# Gamma-BOTTOM-Version2.net
KiCad netlist of a schematic drawn in EAGLE
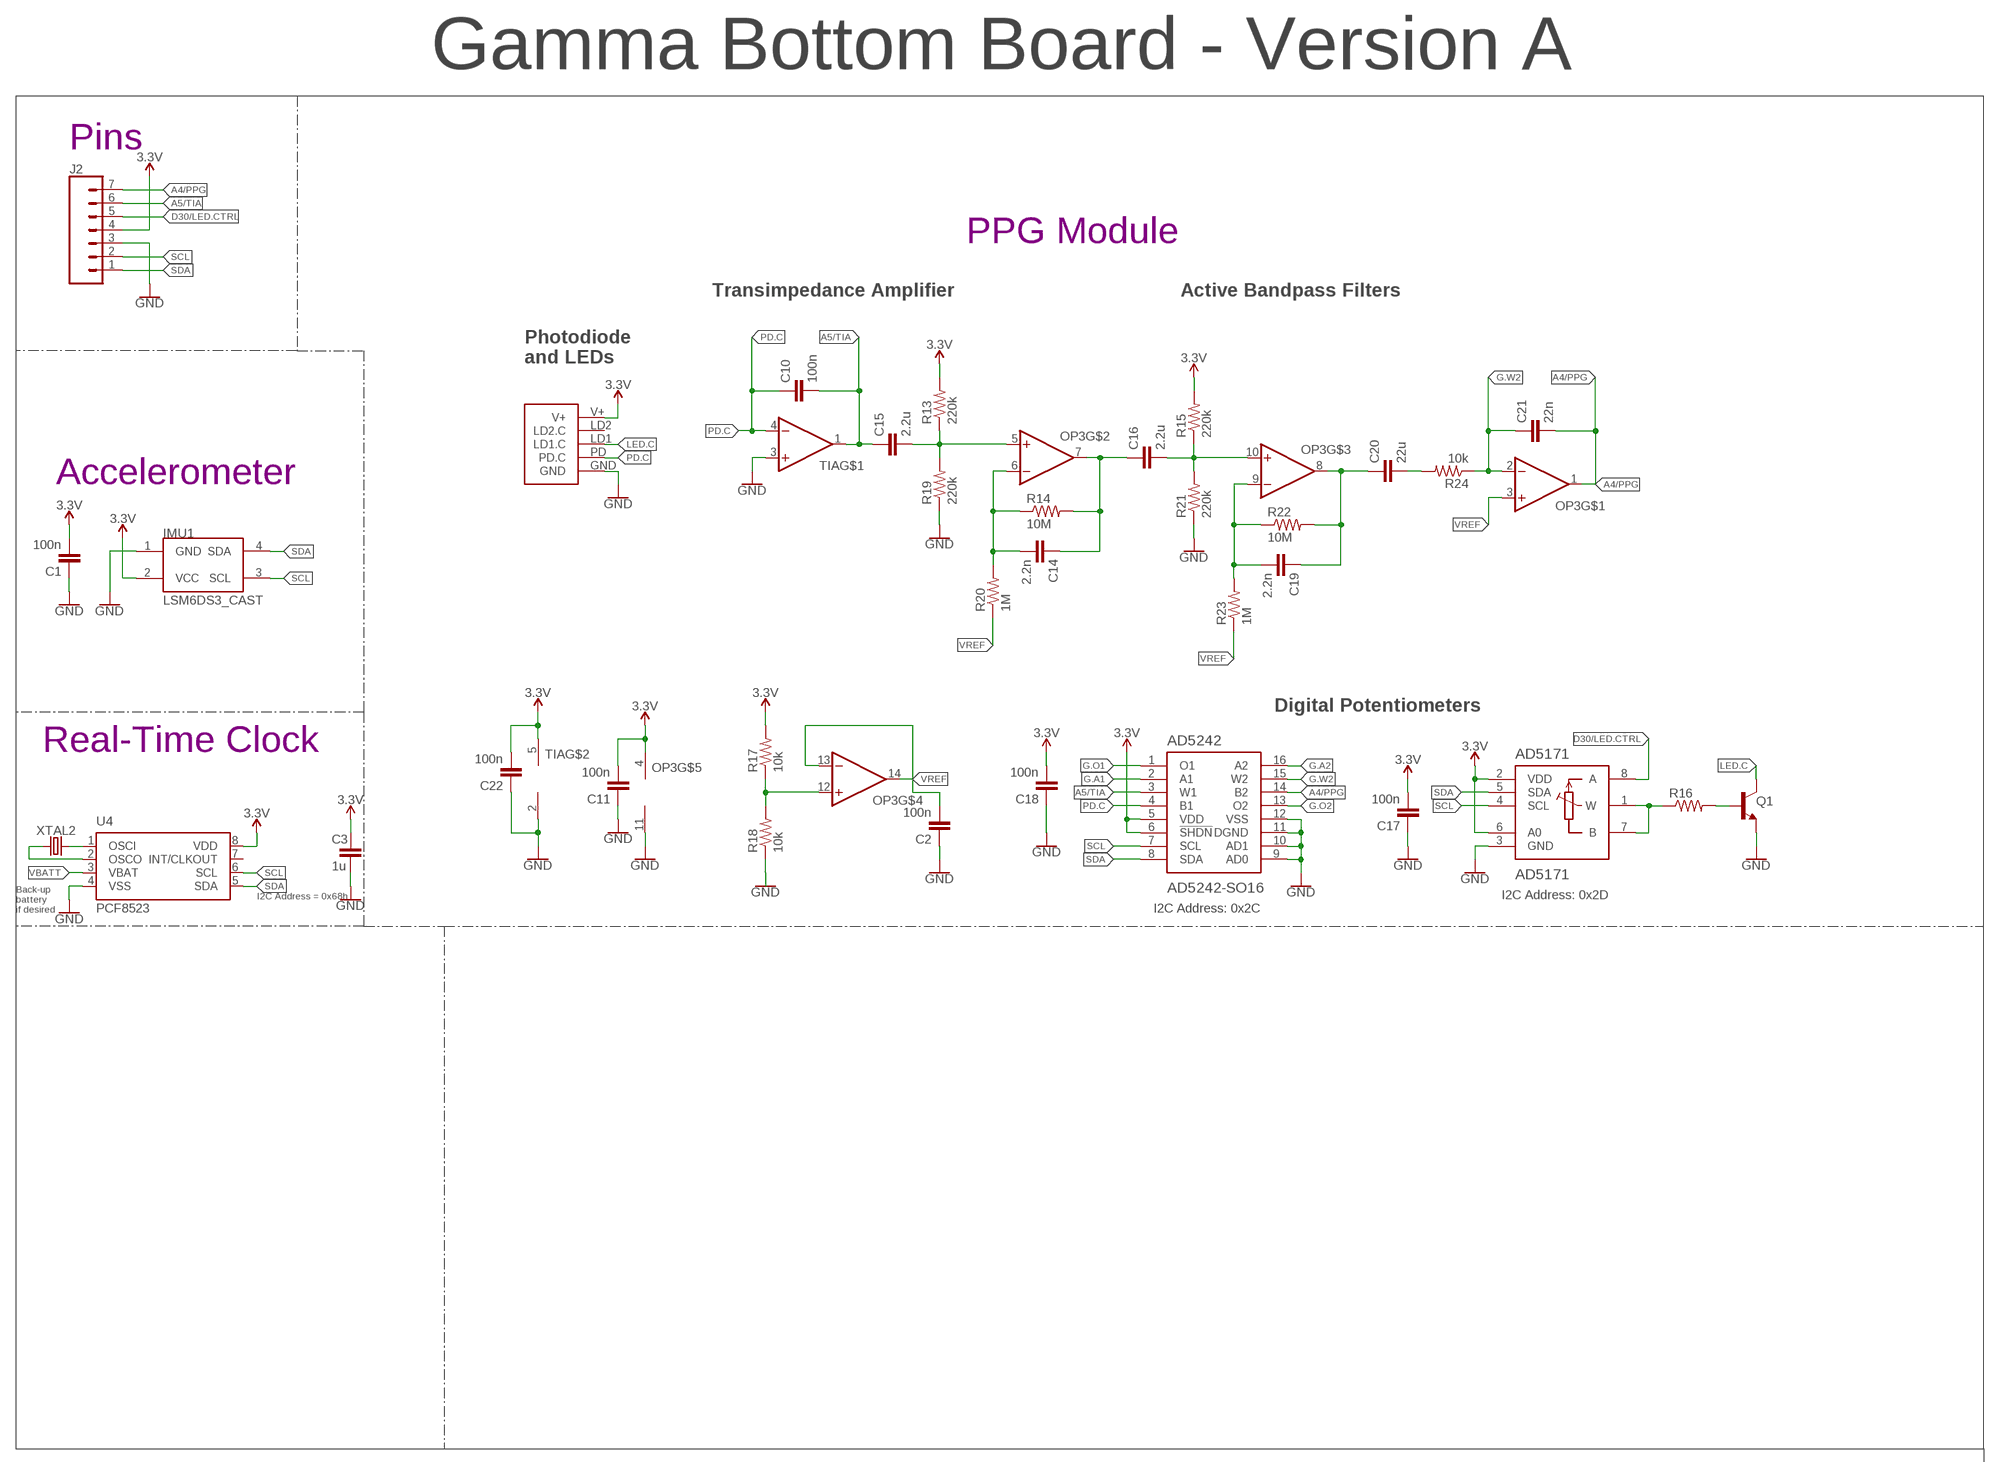
[diagram p0: schematic, sheet 1]

(export (version "E")
  (design (tool "Eeschema 10.0.6"))
  (components
    (comp (ref "AD5171")
      (value "AD5171")
      (footprint "eagle-import:SOT-23-8")
      (libsource (lib "eagle-import") (part "AD5171"))
    )
    (comp (ref "AD5242")
      (value "AD5242-SO16")
      (footprint "eagle-import:SO16")
      (libsource (lib "eagle-import") (part "AD5242-SO16"))
    )
    (comp (ref "C1")
      (value "100n")
      (footprint "eagle-import:C0603")
      (libsource (lib "eagle-import") (part "CAPACITOR0603"))
    )
    (comp (ref "C2")
      (value "100n")
      (footprint "eagle-import:C0603")
      (libsource (lib "eagle-import") (part "CAPACITOR0603"))
    )
    (comp (ref "C3")
      (value "1u")
      (footprint "eagle-import:C0603")
      (libsource (lib "eagle-import") (part "CAPACITOR0603"))
    )
    (comp (ref "C10")
      (value "100n")
      (footprint "eagle-import:C0603")
      (libsource (lib "eagle-import") (part "CAPACITOR0603"))
    )
    (comp (ref "C11")
      (value "100n")
      (footprint "eagle-import:C0603")
      (libsource (lib "eagle-import") (part "CAPACITOR0603"))
    )
    (comp (ref "C14")
      (value "2.2n")
      (footprint "eagle-import:C0603")
      (libsource (lib "eagle-import") (part "CAPACITOR0603"))
    )
    (comp (ref "C15")
      (value "2.2u")
      (footprint "eagle-import:C0603")
      (libsource (lib "eagle-import") (part "CAPACITOR0603"))
    )
    (comp (ref "C16")
      (value "2.2u")
      (footprint "eagle-import:C0603")
      (libsource (lib "eagle-import") (part "CAPACITOR0603"))
    )
    (comp (ref "C17")
      (value "100n")
      (footprint "eagle-import:C0603")
      (libsource (lib "eagle-import") (part "CAPACITOR0603"))
    )
    (comp (ref "C18")
      (value "100n")
      (footprint "eagle-import:C0603")
      (libsource (lib "eagle-import") (part "CAPACITOR0603"))
    )
    (comp (ref "C19")
      (value "2.2n")
      (footprint "eagle-import:C0603")
      (libsource (lib "eagle-import") (part "CAPACITOR0603"))
    )
    (comp (ref "C20")
      (value "22u")
      (footprint "eagle-import:C0603")
      (libsource (lib "eagle-import") (part "CAPACITOR0603"))
    )
    (comp (ref "C21")
      (value "22n")
      (footprint "eagle-import:C0603")
      (libsource (lib "eagle-import") (part "CAPACITOR0603"))
    )
    (comp (ref "C22")
      (value "100n")
      (footprint "eagle-import:C0603")
      (libsource (lib "eagle-import") (part "CAPACITOR0603"))
    )
    (comp (ref "IMU1")
      (value "LSM6DS3_CAST")
      (footprint "eagle-import:LSM6DS3_CAST")
      (libsource (lib "eagle-import") (part "LSM6DS3_CAST"))
    )
    (comp (ref "J2")
      (value "CONN_07-1.27MM")
      (footprint "eagle-import:1X07_1.27MM")
      (libsource (lib "eagle-import") (part "CONN_07-1.27MM"))
    )
    (comp (ref "OP3")
      (value "OP-QUAD-SO14")
      (footprint "eagle-import:SO14")
      (libsource (lib "eagle-import") (part "OP-QUAD-SO14"))
    )
    (comp (ref "Q1")
      (value "NPN-GENERIC")
      (footprint "eagle-import:SOT23-3")
      (libsource (lib "eagle-import") (part "NPN-GENERIC"))
    )
    (comp (ref "R13")
      (value "220k")
      (footprint "eagle-import:R0603")
      (libsource (lib "eagle-import") (part "RESISTOR0603"))
    )
    (comp (ref "R14")
      (value "10M")
      (footprint "eagle-import:R0603")
      (libsource (lib "eagle-import") (part "RESISTOR0603"))
    )
    (comp (ref "R15")
      (value "220k")
      (footprint "eagle-import:R0603")
      (libsource (lib "eagle-import") (part "RESISTOR0603"))
    )
    (comp (ref "R16")
      (value "RESISTOR0603")
      (footprint "eagle-import:R0603")
      (libsource (lib "eagle-import") (part "RESISTOR0603"))
    )
    (comp (ref "R17")
      (value "10k")
      (footprint "eagle-import:R0402")
      (libsource (lib "eagle-import") (part "RESISTOR0402"))
    )
    (comp (ref "R18")
      (value "10k")
      (footprint "eagle-import:R0402")
      (libsource (lib "eagle-import") (part "RESISTOR0402"))
    )
    (comp (ref "R19")
      (value "220k")
      (footprint "eagle-import:R0603")
      (libsource (lib "eagle-import") (part "RESISTOR0603"))
    )
    (comp (ref "R20")
      (value "1M")
      (footprint "eagle-import:R0603")
      (libsource (lib "eagle-import") (part "RESISTOR0603"))
    )
    (comp (ref "R21")
      (value "220k")
      (footprint "eagle-import:R0603")
      (libsource (lib "eagle-import") (part "RESISTOR0603"))
    )
    (comp (ref "R22")
      (value "10M")
      (footprint "eagle-import:R0603")
      (libsource (lib "eagle-import") (part "RESISTOR0603"))
    )
    (comp (ref "R23")
      (value "1M")
      (footprint "eagle-import:R0603")
      (libsource (lib "eagle-import") (part "RESISTOR0603"))
    )
    (comp (ref "R24")
      (value "10k")
      (footprint "eagle-import:R0603")
      (libsource (lib "eagle-import") (part "RESISTOR0603"))
    )
    (comp (ref "TIA")
      (value "OP-SINGLEOT")
      (footprint "eagle-import:SOT23-5")
      (libsource (lib "eagle-import") (part "OP-SINGLEOT"))
    )
    (comp (ref "U$3")
      (value "PPG.MODULE.2")
      (footprint "eagle-import:PPG.MODULE.2")
      (libsource (lib "eagle-import") (part "PPG.MODULE.2"))
    )
    (comp (ref "U4")
      (value "PCF8523")
      (footprint "eagle-import:SO8")
      (libsource (lib "eagle-import") (part "PCF8523"))
    )
    (comp (ref "XTAL2")
      (value "32.7680kHz")
      (footprint "eagle-import:2-SMD.NOLEAD.2.0MMTO1.2MM")
      (fields (field (name "FREQ") "32.7680KHZ"))
      (libsource (lib "eagle-import") (part "CRYSTALECS-.327-12.5-12-C-TR"))
    )
  )
  (nets
    (net (code "1") (name "3.3V") (class "Default")
      (node (ref "AD5171") (pin "2") (pinfunction "VDD_2") (pintype "bidirectional"))
      (node (ref "AD5171") (pin "6") (pinfunction "A0_6") (pintype "bidirectional"))
      (node (ref "AD5242") (pin "5") (pinfunction "VDD_5") (pintype "bidirectional"))
      (node (ref "AD5242") (pin "6") (pinfunction "~{SHDN}_6") (pintype "bidirectional"))
      (node (ref "C1") (pin "2") (pinfunction "2_2") (pintype "passive"))
      (node (ref "C11") (pin "2") (pinfunction "2_2") (pintype "passive"))
      (node (ref "C17") (pin "2") (pinfunction "2_2") (pintype "passive"))
      (node (ref "C18") (pin "2") (pinfunction "2_2") (pintype "passive"))
      (node (ref "C22") (pin "2") (pinfunction "2_2") (pintype "passive"))
      (node (ref "C3") (pin "1") (pinfunction "1_1") (pintype "passive"))
      (node (ref "IMU1") (pin "2") (pinfunction "VCC_2") (pintype "bidirectional"))
      (node (ref "J2") (pin "4") (pinfunction "4_4") (pintype "passive"))
      (node (ref "OP3") (pin "4") (pinfunction "V+_4") (pintype "power_in"))
      (node (ref "R13") (pin "2") (pinfunction "2_2") (pintype "passive"))
      (node (ref "R15") (pin "2") (pinfunction "2_2") (pintype "passive"))
      (node (ref "R17") (pin "2") (pinfunction "2_2") (pintype "passive"))
      (node (ref "TIA") (pin "5") (pinfunction "V+_5") (pintype "power_in"))
      (node (ref "U$3") (pin "V+") (pinfunction "V+_V+") (pintype "bidirectional"))
      (node (ref "U4") (pin "8") (pinfunction "VDD_8") (pintype "power_in"))
    )
    (net (code "2") (name "A4{slash}PPG") (class "Default")
      (node (ref "AD5242") (pin "14") (pinfunction "B2_14") (pintype "bidirectional"))
      (node (ref "C21") (pin "2") (pinfunction "2_2") (pintype "passive"))
      (node (ref "J2") (pin "7") (pinfunction "7_7") (pintype "passive"))
      (node (ref "OP3") (pin "1") (pinfunction "OUT_1") (pintype "output"))
    )
    (net (code "3") (name "A5{slash}TIA") (class "Default")
      (node (ref "AD5242") (pin "3") (pinfunction "W1_3") (pintype "bidirectional"))
      (node (ref "C10") (pin "2") (pinfunction "2_2") (pintype "passive"))
      (node (ref "C15") (pin "1") (pinfunction "1_1") (pintype "passive"))
      (node (ref "J2") (pin "6") (pinfunction "6_6") (pintype "passive"))
      (node (ref "TIA") (pin "1") (pinfunction "OUT_1") (pintype "output"))
    )
    (net (code "4") (name "D30{slash}LED.CTRL") (class "Default")
      (node (ref "AD5171") (pin "8") (pinfunction "A_8") (pintype "bidirectional"))
      (node (ref "J2") (pin "5") (pinfunction "5_5") (pintype "passive"))
    )
    (net (code "5") (name "G.A1") (class "Default")
      (node (ref "AD5242") (pin "2") (pinfunction "A1_2") (pintype "bidirectional"))
    )
    (net (code "6") (name "G.A2") (class "Default")
      (node (ref "AD5242") (pin "16") (pinfunction "A2_16") (pintype "bidirectional"))
    )
    (net (code "7") (name "G.O1") (class "Default")
      (node (ref "AD5242") (pin "1") (pinfunction "O1_1") (pintype "bidirectional"))
    )
    (net (code "8") (name "G.O2") (class "Default")
      (node (ref "AD5242") (pin "13") (pinfunction "O2_13") (pintype "bidirectional"))
    )
    (net (code "9") (name "G.W2") (class "Default")
      (node (ref "AD5242") (pin "15") (pinfunction "W2_15") (pintype "bidirectional"))
      (node (ref "C21") (pin "1") (pinfunction "1_1") (pintype "passive"))
      (node (ref "OP3") (pin "2") (pinfunction "-IN_2") (pintype "input"))
      (node (ref "R24") (pin "1") (pinfunction "1_1") (pintype "passive"))
    )
    (net (code "10") (name "GND") (class "Default")
      (node (ref "AD5171") (pin "3") (pinfunction "GND_3") (pintype "bidirectional"))
      (node (ref "AD5242") (pin "10") (pinfunction "AD1_10") (pintype "bidirectional"))
      (node (ref "AD5242") (pin "11") (pinfunction "DGND_11") (pintype "bidirectional"))
      (node (ref "AD5242") (pin "12") (pinfunction "VSS_12") (pintype "bidirectional"))
      (node (ref "AD5242") (pin "9") (pinfunction "AD0_9") (pintype "bidirectional"))
      (node (ref "C1") (pin "1") (pinfunction "1_1") (pintype "passive"))
      (node (ref "C11") (pin "1") (pinfunction "1_1") (pintype "passive"))
      (node (ref "C17") (pin "1") (pinfunction "1_1") (pintype "passive"))
      (node (ref "C18") (pin "1") (pinfunction "1_1") (pintype "passive"))
      (node (ref "C2") (pin "1") (pinfunction "1_1") (pintype "passive"))
      (node (ref "C22") (pin "1") (pinfunction "1_1") (pintype "passive"))
      (node (ref "C3") (pin "2") (pinfunction "2_2") (pintype "passive"))
      (node (ref "IMU1") (pin "1") (pinfunction "GND_1") (pintype "bidirectional"))
      (node (ref "J2") (pin "3") (pinfunction "3_3") (pintype "passive"))
      (node (ref "OP3") (pin "11") (pinfunction "V-_11") (pintype "power_in"))
      (node (ref "Q1") (pin "2") (pinfunction "E_2") (pintype "passive"))
      (node (ref "R18") (pin "1") (pinfunction "1_1") (pintype "passive"))
      (node (ref "R19") (pin "1") (pinfunction "1_1") (pintype "passive"))
      (node (ref "R21") (pin "1") (pinfunction "1_1") (pintype "passive"))
      (node (ref "TIA") (pin "2") (pinfunction "V-_2") (pintype "power_in"))
      (node (ref "TIA") (pin "3") (pinfunction "+IN_3") (pintype "input"))
      (node (ref "U$3") (pin "GND") (pinfunction "GND_GND") (pintype "bidirectional"))
      (node (ref "U4") (pin "4") (pinfunction "VSS_4") (pintype "power_in"))
    )
    (net (code "11") (name "LED.C") (class "Default")
      (node (ref "Q1") (pin "3") (pinfunction "C_3") (pintype "passive"))
      (node (ref "U$3") (pin "LD1") (pinfunction "LD1.C_LD1") (pintype "bidirectional"))
    )
    (net (code "12") (name "Net-(AD5171-B)") (class "Default")
      (node (ref "AD5171") (pin "1") (pinfunction "W_1") (pintype "bidirectional"))
      (node (ref "AD5171") (pin "7") (pinfunction "B_7") (pintype "bidirectional"))
      (node (ref "R16") (pin "1") (pinfunction "1_1") (pintype "passive"))
    )
    (net (code "13") (name "Net-(C20-Pad2)") (class "Default")
      (node (ref "C20") (pin "2") (pinfunction "2_2") (pintype "passive"))
      (node (ref "R24") (pin "2") (pinfunction "2_2") (pintype "passive"))
    )
    (net (code "14") (name "Net-(OP3B-+IN)") (class "Default")
      (node (ref "C15") (pin "2") (pinfunction "2_2") (pintype "passive"))
      (node (ref "OP3") (pin "5") (pinfunction "+IN_5") (pintype "input"))
      (node (ref "R13") (pin "1") (pinfunction "1_1") (pintype "passive"))
      (node (ref "R19") (pin "2") (pinfunction "2_2") (pintype "passive"))
    )
    (net (code "15") (name "Net-(OP3B--IN)") (class "Default")
      (node (ref "C14") (pin "2") (pinfunction "2_2") (pintype "passive"))
      (node (ref "OP3") (pin "6") (pinfunction "-IN_6") (pintype "input"))
      (node (ref "R14") (pin "1") (pinfunction "1_1") (pintype "passive"))
      (node (ref "R20") (pin "2") (pinfunction "2_2") (pintype "passive"))
    )
    (net (code "16") (name "Net-(OP3B-OUT)") (class "Default")
      (node (ref "C14") (pin "1") (pinfunction "1_1") (pintype "passive"))
      (node (ref "C16") (pin "1") (pinfunction "1_1") (pintype "passive"))
      (node (ref "OP3") (pin "7") (pinfunction "OUT_7") (pintype "output"))
      (node (ref "R14") (pin "2") (pinfunction "2_2") (pintype "passive"))
    )
    (net (code "17") (name "Net-(OP3C-+IN)") (class "Default")
      (node (ref "C16") (pin "2") (pinfunction "2_2") (pintype "passive"))
      (node (ref "OP3") (pin "10") (pinfunction "+IN_10") (pintype "input"))
      (node (ref "R15") (pin "1") (pinfunction "1_1") (pintype "passive"))
      (node (ref "R21") (pin "2") (pinfunction "2_2") (pintype "passive"))
    )
    (net (code "18") (name "Net-(OP3C--IN)") (class "Default")
      (node (ref "C19") (pin "2") (pinfunction "2_2") (pintype "passive"))
      (node (ref "OP3") (pin "9") (pinfunction "-IN_9") (pintype "input"))
      (node (ref "R22") (pin "1") (pinfunction "1_1") (pintype "passive"))
      (node (ref "R23") (pin "2") (pinfunction "2_2") (pintype "passive"))
    )
    (net (code "19") (name "Net-(OP3C-OUT)") (class "Default")
      (node (ref "C19") (pin "1") (pinfunction "1_1") (pintype "passive"))
      (node (ref "C20") (pin "1") (pinfunction "1_1") (pintype "passive"))
      (node (ref "OP3") (pin "8") (pinfunction "OUT_8") (pintype "output"))
      (node (ref "R22") (pin "2") (pinfunction "2_2") (pintype "passive"))
    )
    (net (code "20") (name "Net-(OP3D-+IN)") (class "Default")
      (node (ref "OP3") (pin "12") (pinfunction "+IN_12") (pintype "input"))
      (node (ref "R17") (pin "1") (pinfunction "1_1") (pintype "passive"))
      (node (ref "R18") (pin "2") (pinfunction "2_2") (pintype "passive"))
    )
    (net (code "21") (name "Net-(Q1-B)") (class "Default")
      (node (ref "Q1") (pin "1") (pinfunction "B_1") (pintype "passive"))
      (node (ref "R16") (pin "2") (pinfunction "2_2") (pintype "passive"))
    )
    (net (code "22") (name "Net-(U4-OSCI)") (class "Default")
      (node (ref "U4") (pin "1") (pinfunction "OSCI_1") (pintype "bidirectional"))
      (node (ref "XTAL2") (pin "P$2") (pinfunction "2_P$2") (pintype "passive"))
    )
    (net (code "23") (name "Net-(U4-OSCO)") (class "Default")
      (node (ref "U4") (pin "2") (pinfunction "OSCO_2") (pintype "bidirectional"))
      (node (ref "XTAL2") (pin "P$1") (pinfunction "1_P$1") (pintype "passive"))
    )
    (net (code "24") (name "PD.C") (class "Default")
      (node (ref "AD5242") (pin "4") (pinfunction "B1_4") (pintype "bidirectional"))
      (node (ref "C10") (pin "1") (pinfunction "1_1") (pintype "passive"))
      (node (ref "TIA") (pin "4") (pinfunction "-IN_4") (pintype "input"))
      (node (ref "U$3") (pin "PD") (pinfunction "PD.C_PD") (pintype "bidirectional"))
    )
    (net (code "25") (name "SCL") (class "Default")
      (node (ref "AD5171") (pin "4") (pinfunction "SCL_4") (pintype "bidirectional"))
      (node (ref "AD5242") (pin "7") (pinfunction "SCL_7") (pintype "bidirectional"))
      (node (ref "IMU1") (pin "3") (pinfunction "SCL_3") (pintype "bidirectional"))
      (node (ref "J2") (pin "2") (pinfunction "2_2") (pintype "passive"))
      (node (ref "U4") (pin "6") (pinfunction "SCL_6") (pintype "bidirectional"))
    )
    (net (code "26") (name "SDA") (class "Default")
      (node (ref "AD5171") (pin "5") (pinfunction "SDA_5") (pintype "bidirectional"))
      (node (ref "AD5242") (pin "8") (pinfunction "SDA_8") (pintype "bidirectional"))
      (node (ref "IMU1") (pin "4") (pinfunction "SDA_4") (pintype "bidirectional"))
      (node (ref "J2") (pin "1") (pinfunction "1_1") (pintype "passive"))
      (node (ref "U4") (pin "5") (pinfunction "SDA_5") (pintype "bidirectional"))
    )
    (net (code "27") (name "VBATT") (class "Default")
      (node (ref "U4") (pin "3") (pinfunction "VBAT_3") (pintype "power_in"))
    )
    (net (code "28") (name "VREF") (class "Default")
      (node (ref "C2") (pin "2") (pinfunction "2_2") (pintype "passive"))
      (node (ref "OP3") (pin "13") (pinfunction "-IN_13") (pintype "input"))
      (node (ref "OP3") (pin "14") (pinfunction "OUT_14") (pintype "output"))
      (node (ref "OP3") (pin "3") (pinfunction "+IN_3") (pintype "input"))
      (node (ref "R20") (pin "1") (pinfunction "1_1") (pintype "passive"))
      (node (ref "R23") (pin "1") (pinfunction "1_1") (pintype "passive"))
    )
    (net (code "29") (name "unconnected-(U$3-LD2.C-PadLD2)") (class "Default")
      (node (ref "U$3") (pin "LD2") (pinfunction "LD2.C_LD2") (pintype "bidirectional"))
    )
    (net (code "30") (name "unconnected-(U4-INT{slash}CLKOUT-Pad7)") (class "Default")
      (node (ref "U4") (pin "7") (pinfunction "INT/CLKOUT_7") (pintype "bidirectional"))
    )
  )
)
